# UART.net
KiCad netlist of a schematic drawn in Altium Designer
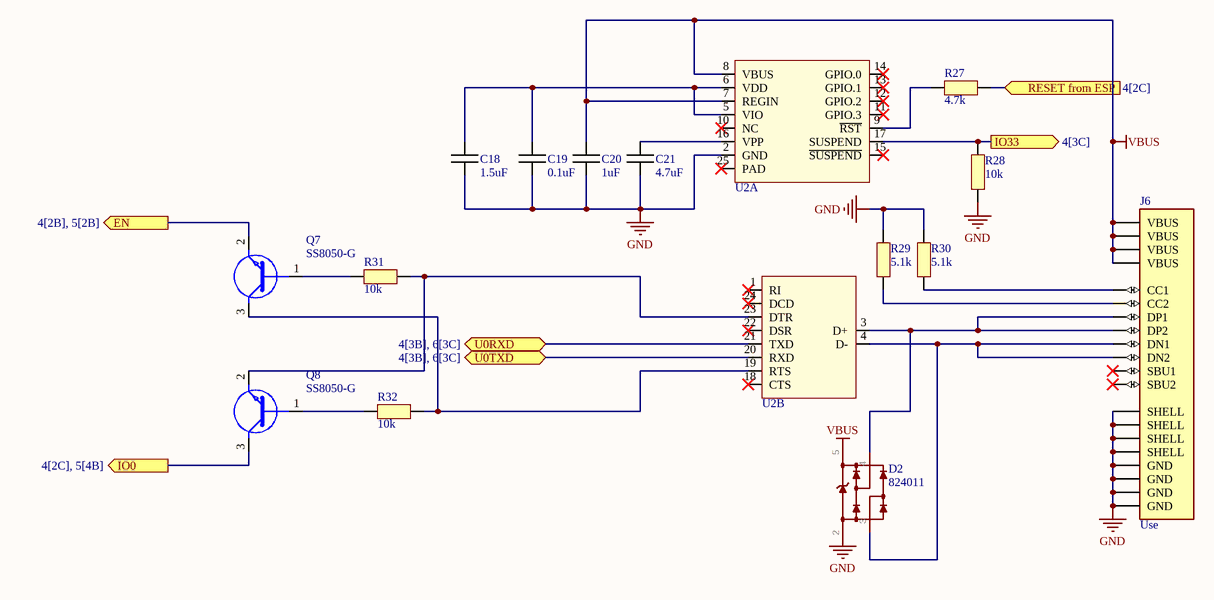
[diagram p0: UART.SchDoc]

(export (version "E")
  (design (tool "Eeschema 10.0.6"))
  (components
    (comp (ref "C18")
      (value "1.5uF")
      (footprint "CAPC1005X06N")
      (libsource (lib "SCHLibrary") (part "Capacitor"))
    )
    (comp (ref "C19")
      (value "0.1uF")
      (footprint "CAPC1005X06N")
      (libsource (lib "SCHLibrary") (part "Capacitor"))
    )
    (comp (ref "C20")
      (value "1uF")
      (footprint "CAPC1005X06N")
      (libsource (lib "SCHLibrary") (part "Capacitor"))
    )
    (comp (ref "C21")
      (value "4.7uF")
      (footprint "CAPC1005X06N")
      (libsource (lib "SCHLibrary") (part "Capacitor"))
    )
    (comp (ref "D2") (value "824011") (footprint "824011") (libsource (lib "SCHLibrary") (part "824011")))
    (comp (ref "J6")
      (value "Use")
      (footprint "USB4085-GF-A")
      (description "Connecteurs USB USB Type C, 2.0, Rec, TH , G/F, RA , Top Mnt, T & R")
      (libsource (lib "SCHLibrary") (part "USB4085-GF-A"))
    )
    (comp (ref "Q7")
      (value "SS8050-G")
      (footprint "SS8050-G")
      (description "Bipolar Transistors - BJT NPN TRANSISTOR 1.5A 40V")
      (libsource (lib "SCHLibrary") (part "SS8050-G"))
    )
    (comp (ref "Q8")
      (value "SS8050-G")
      (footprint "SS8050-G")
      (description "Bipolar Transistors - BJT NPN TRANSISTOR 1.5A 40V")
      (libsource (lib "SCHLibrary") (part "SS8050-G"))
    )
    (comp (ref "R27")
      (value "4.7k")
      (footprint "RESC1005X06N")
      (libsource (lib "SCHLibrary") (part "Resistor"))
    )
    (comp (ref "R28") (value "10k") (footprint "RESC1005X06N") (libsource (lib "") (part "Resistor_2")))
    (comp (ref "R29") (value "5.1k") (footprint "RESC1005X06N") (libsource (lib "") (part "Resistor_1")))
    (comp (ref "R30") (value "5.1k") (footprint "RESC1005X06N") (libsource (lib "") (part "Resistor_1")))
    (comp (ref "R31")
      (value "10k")
      (footprint "RESC1005X06N")
      (libsource (lib "SCHLibrary") (part "Resistor"))
    )
    (comp (ref "R32")
      (value "10k")
      (footprint "RESC1005X06N")
      (libsource (lib "SCHLibrary") (part "Resistor"))
    )
    (comp (ref "U2")
      (value "CP2104-F03-GM")
      (footprint "PQFN50P400X400X80_HS-25N")
      (description "USB Bridge, USB to UART USB 2.0 UART Interface 24-QFN (4x4)")
      (libsource (lib "SCHLibrary") (part "USBBridge"))
    )
  )
  (nets
    (net (code "1") (name "/EN") (class "Default")
      (node (ref "Q7") (pin "2") (pinfunction "E_2") (pintype "passive"))
    )
    (net (code "2") (name "/IO0") (class "Default")
      (node (ref "Q8") (pin "3") (pinfunction "C_3") (pintype "passive"))
    )
    (net (code "3") (name "/IO33") (class "Default")
      (node (ref "R28") (pin "1") (pinfunction "1_1") (pintype "passive"))
      (node (ref "U2") (pin "17") (pinfunction "SUSPEND_17") (pintype "passive"))
    )
    (net (code "4") (name "/RESET from ESP") (class "Default")
      (node (ref "R27") (pin "1") (pinfunction "1_1") (pintype "passive"))
    )
    (net (code "5") (name "/U0RXD") (class "Default")
      (node (ref "U2") (pin "21") (pinfunction "TXD_21") (pintype "passive"))
    )
    (net (code "6") (name "/U0TXD") (class "Default")
      (node (ref "U2") (pin "20") (pinfunction "RXD_20") (pintype "passive"))
    )
    (net (code "7") (name "GND") (class "Default")
      (node (ref "C18") (pin "2") (pinfunction "2_2") (pintype "passive"))
      (node (ref "C19") (pin "2") (pinfunction "2_2") (pintype "passive"))
      (node (ref "C20") (pin "2") (pinfunction "2_2") (pintype "passive"))
      (node (ref "C21") (pin "2") (pinfunction "2_2") (pintype "passive"))
      (node (ref "D2") (pin "2") (pinfunction "GND_2") (pintype "power_in"))
      (node (ref "J6") (pin "A1") (pinfunction "GND_A1") (pintype "power_in"))
      (node (ref "J6") (pin "A12") (pinfunction "GND_A12") (pintype "power_in"))
      (node (ref "J6") (pin "B1") (pinfunction "GND_B1") (pintype "power_in"))
      (node (ref "J6") (pin "B12") (pinfunction "GND_B12") (pintype "power_in"))
      (node (ref "J6") (pin "S1") (pinfunction "SHELL_S1") (pintype "passive"))
      (node (ref "J6") (pin "S2") (pinfunction "SHELL_S2") (pintype "passive"))
      (node (ref "J6") (pin "S3") (pinfunction "SHELL_S3") (pintype "passive"))
      (node (ref "J6") (pin "S4") (pinfunction "SHELL_S4") (pintype "passive"))
      (node (ref "R28") (pin "2") (pinfunction "2_2") (pintype "passive"))
      (node (ref "R29") (pin "2") (pinfunction "2_2") (pintype "passive"))
      (node (ref "R30") (pin "2") (pinfunction "2_2") (pintype "passive"))
      (node (ref "U2") (pin "2") (pinfunction "GND_2") (pintype "passive"))
    )
    (net (code "8") (name "Net-(D2-1)") (class "Default")
      (node (ref "D2") (pin "3") (pinfunction "1_3") (pintype "passive"))
      (node (ref "J6") (pin "A7") (pinfunction "DN1_A7") (pintype "bidirectional"))
      (node (ref "J6") (pin "B7") (pinfunction "DN2_B7") (pintype "bidirectional"))
      (node (ref "U2") (pin "4") (pinfunction "D-_4") (pintype "passive"))
    )
    (net (code "9") (name "Net-(D2-2)") (class "Default")
      (node (ref "D2") (pin "4") (pinfunction "2_4") (pintype "passive"))
      (node (ref "J6") (pin "A6") (pinfunction "DP1_A6") (pintype "bidirectional"))
      (node (ref "J6") (pin "B6") (pinfunction "DP2_B6") (pintype "bidirectional"))
      (node (ref "U2") (pin "3") (pinfunction "D+_3") (pintype "passive"))
    )
    (net (code "10") (name "Net-(J6-CC1)") (class "Default")
      (node (ref "J6") (pin "A5") (pinfunction "CC1_A5") (pintype "bidirectional"))
      (node (ref "R30") (pin "1") (pinfunction "1_1") (pintype "passive"))
    )
    (net (code "11") (name "Net-(J6-CC2)") (class "Default")
      (node (ref "J6") (pin "B5") (pinfunction "CC2_B5") (pintype "bidirectional"))
      (node (ref "R29") (pin "1") (pinfunction "1_1") (pintype "passive"))
    )
    (net (code "12") (name "Net-(Q7-B)") (class "Default")
      (node (ref "Q7") (pin "1") (pinfunction "B_1") (pintype "passive"))
      (node (ref "R31") (pin "2") (pinfunction "2_2") (pintype "passive"))
    )
    (net (code "13") (name "Net-(Q7-C)") (class "Default")
      (node (ref "Q7") (pin "3") (pinfunction "C_3") (pintype "passive"))
      (node (ref "R32") (pin "1") (pinfunction "1_1") (pintype "passive"))
      (node (ref "U2") (pin "19") (pinfunction "RTS_19") (pintype "passive"))
    )
    (net (code "14") (name "Net-(Q8-B)") (class "Default")
      (node (ref "Q8") (pin "1") (pinfunction "B_1") (pintype "passive"))
      (node (ref "R32") (pin "2") (pinfunction "2_2") (pintype "passive"))
    )
    (net (code "15") (name "Net-(Q8-E)") (class "Default")
      (node (ref "Q8") (pin "2") (pinfunction "E_2") (pintype "passive"))
      (node (ref "R31") (pin "1") (pinfunction "1_1") (pintype "passive"))
      (node (ref "U2") (pin "23") (pinfunction "DTR_23") (pintype "passive"))
    )
    (net (code "16") (name "Net-(U2A-VDD)") (class "Default")
      (node (ref "C18") (pin "1") (pinfunction "1_1") (pintype "passive"))
      (node (ref "C19") (pin "1") (pinfunction "1_1") (pintype "passive"))
      (node (ref "U2") (pin "5") (pinfunction "VIO_5") (pintype "passive"))
      (node (ref "U2") (pin "6") (pinfunction "VDD_6") (pintype "passive"))
    )
    (net (code "17") (name "Net-(U2A-VPP)") (class "Default")
      (node (ref "C21") (pin "1") (pinfunction "1_1") (pintype "passive"))
      (node (ref "U2") (pin "16") (pinfunction "VPP_16") (pintype "passive"))
    )
    (net (code "18") (name "Net-(U2A-~{RST})") (class "Default")
      (node (ref "R27") (pin "2") (pinfunction "2_2") (pintype "passive"))
      (node (ref "U2") (pin "9") (pinfunction "~{RST}_9") (pintype "passive"))
    )
    (net (code "19") (name "VBUS") (class "Default")
      (node (ref "C20") (pin "1") (pinfunction "1_1") (pintype "passive"))
      (node (ref "D2") (pin "5") (pinfunction "VDD_5") (pintype "power_in"))
      (node (ref "J6") (pin "A4") (pinfunction "VBUS_A4") (pintype "power_in"))
      (node (ref "J6") (pin "A9") (pinfunction "VBUS_A9") (pintype "power_in"))
      (node (ref "J6") (pin "B4") (pinfunction "VBUS_B4") (pintype "power_in"))
      (node (ref "J6") (pin "B9") (pinfunction "VBUS_B9") (pintype "power_in"))
      (node (ref "U2") (pin "7") (pinfunction "REGIN_7") (pintype "passive"))
      (node (ref "U2") (pin "8") (pinfunction "VBUS_8") (pintype "passive"))
    )
    (net (code "20") (name "unconnected-(J6-SBU1-PadA8)") (class "Default")
      (node (ref "J6") (pin "A8") (pinfunction "SBU1_A8") (pintype "bidirectional+no_connect"))
    )
    (net (code "21") (name "unconnected-(J6-SBU2-PadB8)") (class "Default")
      (node (ref "J6") (pin "B8") (pinfunction "SBU2_B8") (pintype "bidirectional+no_connect"))
    )
    (net (code "22") (name "unconnected-(U2A-GPIO.0-Pad14)") (class "Default")
      (node (ref "U2") (pin "14") (pinfunction "GPIO.0_14") (pintype "passive+no_connect"))
    )
    (net (code "23") (name "unconnected-(U2A-GPIO.1-Pad13)") (class "Default")
      (node (ref "U2") (pin "13") (pinfunction "GPIO.1_13") (pintype "passive+no_connect"))
    )
    (net (code "24") (name "unconnected-(U2A-GPIO.2-Pad12)") (class "Default")
      (node (ref "U2") (pin "12") (pinfunction "GPIO.2_12") (pintype "passive+no_connect"))
    )
    (net (code "25") (name "unconnected-(U2A-GPIO.3-Pad11)") (class "Default")
      (node (ref "U2") (pin "11") (pinfunction "GPIO.3_11") (pintype "passive+no_connect"))
    )
    (net (code "26") (name "unconnected-(U2A-NC-Pad10)") (class "Default")
      (node (ref "U2") (pin "10") (pinfunction "NC_10") (pintype "passive+no_connect"))
    )
    (net (code "27") (name "unconnected-(U2A-PAD-Pad25)") (class "Default")
      (node (ref "U2") (pin "25") (pinfunction "PAD_25") (pintype "passive+no_connect"))
    )
    (net (code "28") (name "unconnected-(U2A-~{SUSPEND}-Pad15)") (class "Default")
      (node (ref "U2") (pin "15") (pinfunction "~{SUSPEND}_15") (pintype "passive+no_connect"))
    )
    (net (code "29") (name "unconnected-(U2B-CTS-Pad18)") (class "Default")
      (node (ref "U2") (pin "18") (pinfunction "CTS_18") (pintype "passive+no_connect"))
    )
    (net (code "30") (name "unconnected-(U2B-DCD-Pad24)") (class "Default")
      (node (ref "U2") (pin "24") (pinfunction "DCD_24") (pintype "passive+no_connect"))
    )
    (net (code "31") (name "unconnected-(U2B-DSR-Pad22)") (class "Default")
      (node (ref "U2") (pin "22") (pinfunction "DSR_22") (pintype "passive+no_connect"))
    )
    (net (code "32") (name "unconnected-(U2B-RI-Pad1)") (class "Default")
      (node (ref "U2") (pin "1") (pinfunction "RI_1") (pintype "passive+no_connect"))
    )
  )
)
